# RemoteSch_V2.net
KiCad netlist of a schematic drawn in Altium Designer
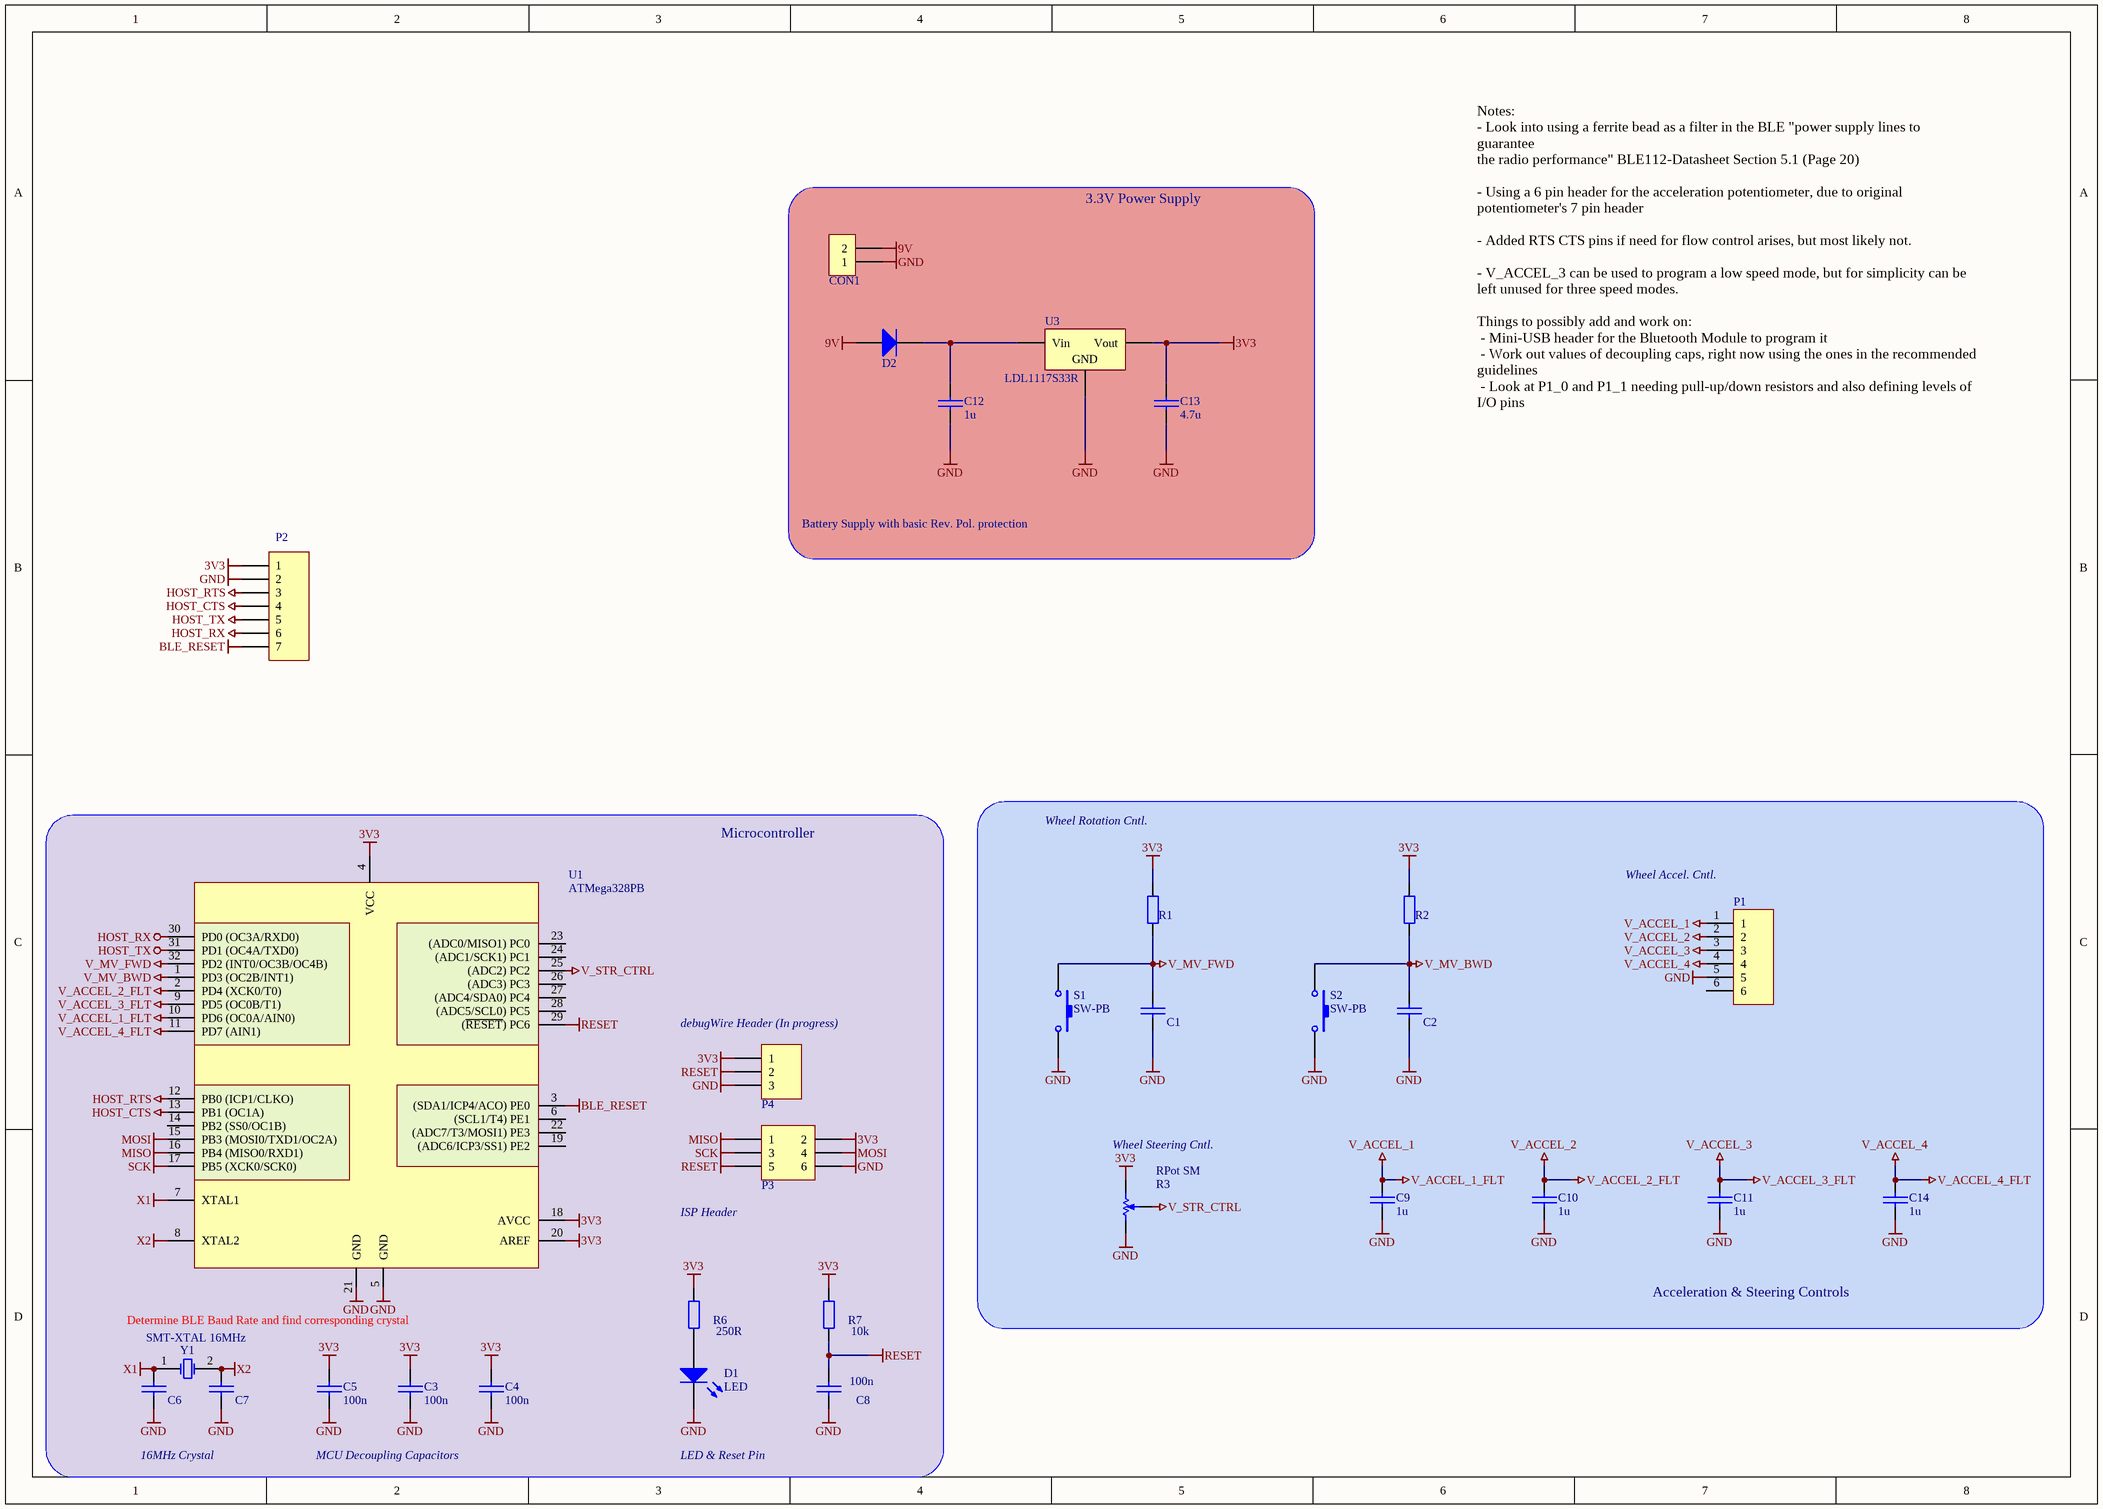
[diagram p0: RemoteSch_V2.SchDoc]

(export (version "E")
  (design (tool "Eeschema 10.0.6"))
  (components
    (comp (ref "C1")
      (value "Capacitor 0805")
      (footprint "C0805")
      (description "CCAP0805")
      (libsource (lib "CommonDevices_V1") (part "CCAP0805"))
    )
    (comp (ref "C2")
      (value "Capacitor 0805")
      (footprint "C0805")
      (description "CCAP0805")
      (libsource (lib "CommonDevices_V1") (part "CCAP0805"))
    )
    (comp (ref "C3")
      (value "100n")
      (footprint "C1206")
      (description "CAP CER 0.1UF 100V C0G 1206")
      (fields (field (name "MPN") "C3216C0G2A104J160AC") (field (name "MANUFACTURER") "TDK Corporation"))
      (libsource (lib "E209_Lib") (part "Cap CER Decoup C3216C0G2A104J160AC"))
    )
    (comp (ref "C4")
      (value "100n")
      (footprint "C1206")
      (description "CAP CER 0.1UF 100V C0G 1206")
      (fields (field (name "MPN") "C3216C0G2A104J160AC") (field (name "MANUFACTURER") "TDK Corporation"))
      (libsource (lib "E209_Lib") (part "Cap CER Decoup C3216C0G2A104J160AC"))
    )
    (comp (ref "C5")
      (value "100n")
      (footprint "C1206")
      (description "CAP CER 0.1UF 100V C0G 1206")
      (fields (field (name "MPN") "C3216C0G2A104J160AC") (field (name "MANUFACTURER") "TDK Corporation"))
      (libsource (lib "E209_Lib") (part "Cap CER Decoup C3216C0G2A104J160AC"))
    )
    (comp (ref "C6")
      (value "CCAP1210")
      (footprint "C1210")
      (fields (field (name "MPN") "?"))
      (libsource (lib "E209_Lib") (part "CCAP1210"))
    )
    (comp (ref "C7")
      (value "CCAP1210")
      (footprint "C1210")
      (fields (field (name "MPN") "?"))
      (libsource (lib "E209_Lib") (part "CCAP1210"))
    )
    (comp (ref "C8")
      (value "100n")
      (footprint "C1210")
      (description "CCAP1210")
      (libsource (lib "CommonDevices_V1") (part "CCAP1210"))
    )
    (comp (ref "C9")
      (value "1u")
      (footprint "C0805")
      (description "CCAP0805")
      (libsource (lib "CommonDevices_V1") (part "CCAP0805"))
    )
    (comp (ref "C10")
      (value "1u")
      (footprint "C0805")
      (description "CCAP0805")
      (libsource (lib "CommonDevices_V1") (part "CCAP0805"))
    )
    (comp (ref "C11")
      (value "1u")
      (footprint "C0805")
      (description "CCAP0805")
      (libsource (lib "CommonDevices_V1") (part "CCAP0805"))
    )
    (comp (ref "C12")
      (value "1u")
      (footprint "C1210")
      (description "CAP CER 2.2UF 100V X7R 1210")
      (fields (field (name "MPN") "CL32B225KCJSNNE") (field (name "MANUFACTURER") "AVX Corporation"))
      (libsource (lib "E209_Lib") (part "Cap CER HF DC-Link CL32B225KCJSNNE"))
    )
    (comp (ref "C13")
      (value "4.7u")
      (footprint "C1210")
      (description "CAP CER 2.2UF 100V X7R 1210")
      (fields (field (name "MPN") "CL32B225KCJSNNE") (field (name "MANUFACTURER") "AVX Corporation"))
      (libsource (lib "E209_Lib") (part "Cap CER HF DC-Link CL32B225KCJSNNE"))
    )
    (comp (ref "C14")
      (value "1u")
      (footprint "C0805")
      (description "CCAP0805")
      (libsource (lib "CommonDevices_V1") (part "CCAP0805"))
    )
    (comp (ref "CON1")
      (value "Header 2X1")
      (footprint "HDR2X1_2P54")
      (libsource (lib "CommonDevices_V1") (part "HDR2X1"))
    )
    (comp (ref "D1") (value "LED") (footprint "R0805") (libsource (lib "CommonDevices_V1") (part "LED")))
    (comp (ref "D2") (value "Diode") (footprint "DAX4") (libsource (lib "CommonDevices_V1") (part "Diode")))
    (comp (ref "P1")
      (value "Header 6X1")
      (footprint "HDR6X1_2P54")
      (description "Header, 6-Pin")
      (fields (field (name "PUBLISHER") "Altium Limited"))
      (libsource (lib "CommonDevices_V1") (part "HDR6X1"))
    )
    (comp (ref "P2")
      (value "Header 7")
      (footprint "HDR1X7")
      (description "Header, 7-Pin")
      (fields (field (name "PUBLISHER") "Altium Limited"))
      (libsource (lib "Miscellaneous Connectors") (part "Header 7"))
    )
    (comp (ref "P3")
      (value "HDR3X2")
      (footprint "HDR2X3_2P54")
      (description "Header, 3-Pin, Dual row")
      (libsource (lib "CommonDevices_V1") (part "HDR3X2"))
    )
    (comp (ref "P4")
      (value "Header 3")
      (footprint "HDR1X3")
      (description "Header, 3-Pin")
      (fields (field (name "PUBLISHER") "Altium Limited"))
      (libsource (lib "Miscellaneous Connectors") (part "Header 3"))
    )
    (comp (ref "R1")
      (value "Resistor 0805")
      (footprint "R0805")
      (description "RES0805")
      (libsource (lib "CommonDevices_V1") (part "RES0805"))
    )
    (comp (ref "R2")
      (value "Resistor 0805")
      (footprint "R0805")
      (description "RES0805")
      (libsource (lib "CommonDevices_V1") (part "RES0805"))
    )
    (comp (ref "R3")
      (value "RPot SM")
      (footprint "POT4MM-2")
      (description "Square Trimming Potentiometer")
      (fields (field (name "PUBLISHER") "Altium Limited"))
      (libsource (lib "Miscellaneous Devices") (part "RPot SM"))
    )
    (comp (ref "R6")
      (value "250R")
      (footprint "R1206")
      (description "RES1206")
      (libsource (lib "CommonDevices_V1") (part "RES1206"))
    )
    (comp (ref "R7")
      (value "10k")
      (footprint "R1206")
      (description "RES1206")
      (libsource (lib "CommonDevices_V1") (part "RES1206"))
    )
    (comp (ref "S1")
      (value "SW-PB")
      (footprint "SPST-2")
      (description "Switch")
      (fields (field (name "PUBLISHER") "Altium Limited"))
      (libsource (lib "Miscellaneous Devices") (part "SW-PB"))
    )
    (comp (ref "S2")
      (value "SW-PB")
      (footprint "SPST-2")
      (description "Switch")
      (fields (field (name "PUBLISHER") "Altium Limited"))
      (libsource (lib "Miscellaneous Devices") (part "SW-PB"))
    )
    (comp (ref "U1")
      (value "ATMega328PB")
      (footprint "TQFP32")
      (description "IC MCU 8BIT 32KB FLASH 32TQFP")
      (libsource (lib "CommonDevices_V1") (part "ATMega328PB"))
    )
    (comp (ref "U3")
      (value "LDL1117S33R")
      (footprint "SOT223L")
      (description "IC REG LINEAR 3.3V 1.2A SOT223")
      (fields (field (name "MANUFACTURER") "STMicroelectronics"))
      (libsource (lib "E209_Lib") (part "LDO LDL1117S33R"))
    )
    (comp (ref "Y1")
      (value "SMT-XTAL 16MHz")
      (footprint "HC49-US")
      (description "9C-16.000MAAJ-T crystal 16.0000MHZ 18PF SMD")
      (fields
        (field (name "MANUFACTURER") "TXC CORPORATION")
        (field (name "MANUFACTURER PART NUMBER") "9C-16.000MAAJ-T")
      )
      (libsource (lib "EE209_Library") (part "TXC9C-16_XTAL_SMT"))
    )
  )
  (nets
    (net (code "1") (name "3V3") (class "Default")
      (node (ref "C13") (pin "2") (pinfunction "2_2") (pintype "passive"))
      (node (ref "C3") (pin "2") (pinfunction "2_2") (pintype "passive"))
      (node (ref "C4") (pin "2") (pinfunction "2_2") (pintype "passive"))
      (node (ref "C5") (pin "2") (pinfunction "2_2") (pintype "passive"))
      (node (ref "P2") (pin "1") (pinfunction "1_1") (pintype "passive"))
      (node (ref "P3") (pin "2") (pinfunction "2_2") (pintype "passive"))
      (node (ref "P4") (pin "1") (pinfunction "1_1") (pintype "passive"))
      (node (ref "R1") (pin "1") (pinfunction "1_1") (pintype "passive"))
      (node (ref "R2") (pin "1") (pinfunction "1_1") (pintype "passive"))
      (node (ref "R3") (pin "CW") (pinfunction "+_CW") (pintype "passive"))
      (node (ref "R6") (pin "2") (pinfunction "2_2") (pintype "passive"))
      (node (ref "R7") (pin "2") (pinfunction "2_2") (pintype "passive"))
      (node (ref "U1") (pin "18") (pinfunction "AVCC_18") (pintype "passive"))
      (node (ref "U1") (pin "20") (pinfunction "AREF_20") (pintype "passive"))
      (node (ref "U1") (pin "4") (pinfunction "VCC_4") (pintype "passive"))
      (node (ref "U3") (pin "2") (pinfunction "Vout_2") (pintype "passive"))
    )
    (net (code "2") (name "9V") (class "Default")
      (node (ref "CON1") (pin "2") (pinfunction "2_2") (pintype "passive"))
      (node (ref "D2") (pin "1") (pinfunction "1_1") (pintype "passive"))
    )
    (net (code "3") (name "BLE_RESET") (class "Default")
      (node (ref "P2") (pin "7") (pinfunction "7_7") (pintype "passive"))
      (node (ref "U1") (pin "3") (pinfunction "(SDA1/ICP4/ACO)_PE0_3") (pintype "passive"))
    )
    (net (code "4") (name "GND") (class "Default")
      (node (ref "C1") (pin "1") (pinfunction "1_1") (pintype "passive"))
      (node (ref "C10") (pin "1") (pinfunction "1_1") (pintype "passive"))
      (node (ref "C11") (pin "1") (pinfunction "1_1") (pintype "passive"))
      (node (ref "C12") (pin "1") (pinfunction "1_1") (pintype "passive"))
      (node (ref "C13") (pin "1") (pinfunction "1_1") (pintype "passive"))
      (node (ref "C14") (pin "1") (pinfunction "1_1") (pintype "passive"))
      (node (ref "C2") (pin "1") (pinfunction "1_1") (pintype "passive"))
      (node (ref "C3") (pin "1") (pinfunction "1_1") (pintype "passive"))
      (node (ref "C4") (pin "1") (pinfunction "1_1") (pintype "passive"))
      (node (ref "C5") (pin "1") (pinfunction "1_1") (pintype "passive"))
      (node (ref "C6") (pin "1") (pinfunction "1_1") (pintype "passive"))
      (node (ref "C7") (pin "1") (pinfunction "1_1") (pintype "passive"))
      (node (ref "C8") (pin "1") (pinfunction "1_1") (pintype "passive"))
      (node (ref "C9") (pin "1") (pinfunction "1_1") (pintype "passive"))
      (node (ref "CON1") (pin "1") (pinfunction "1_1") (pintype "passive"))
      (node (ref "D1") (pin "2") (pinfunction "K_2") (pintype "passive"))
      (node (ref "P1") (pin "5") (pinfunction "5_5") (pintype "passive"))
      (node (ref "P2") (pin "2") (pinfunction "2_2") (pintype "passive"))
      (node (ref "P3") (pin "6") (pinfunction "6_6") (pintype "passive"))
      (node (ref "P4") (pin "3") (pinfunction "3_3") (pintype "passive"))
      (node (ref "R3") (pin "CCW") (pinfunction "-_CCW") (pintype "passive"))
      (node (ref "S1") (pin "2") (pinfunction "2_2") (pintype "passive"))
      (node (ref "S2") (pin "2") (pinfunction "2_2") (pintype "passive"))
      (node (ref "U3") (pin "1") (pinfunction "GND_1") (pintype "passive"))
    )
    (net (code "5") (name "HOST_CTS") (class "Default")
      (node (ref "P2") (pin "4") (pinfunction "4_4") (pintype "passive"))
      (node (ref "U1") (pin "13") (pinfunction "PB1_(OC1A)_13") (pintype "passive"))
    )
    (net (code "6") (name "HOST_RTS") (class "Default")
      (node (ref "P2") (pin "3") (pinfunction "3_3") (pintype "passive"))
      (node (ref "U1") (pin "12") (pinfunction "PB0_(ICP1/CLKO)_12") (pintype "passive"))
    )
    (net (code "7") (name "HOST_RX") (class "Default")
      (node (ref "P2") (pin "6") (pinfunction "6_6") (pintype "passive"))
      (node (ref "U1") (pin "30") (pinfunction "PD0_(OC3A/RXD0)_30") (pintype "passive"))
    )
    (net (code "8") (name "HOST_TX") (class "Default")
      (node (ref "P2") (pin "5") (pinfunction "5_5") (pintype "passive"))
      (node (ref "U1") (pin "31") (pinfunction "PD1_(OC4A/TXD0)_31") (pintype "passive"))
    )
    (net (code "9") (name "MISO") (class "Default")
      (node (ref "P3") (pin "1") (pinfunction "1_1") (pintype "passive"))
      (node (ref "U1") (pin "16") (pinfunction "PB4_(MISO0/RXD1)_16") (pintype "passive"))
    )
    (net (code "10") (name "MOSI") (class "Default")
      (node (ref "P3") (pin "4") (pinfunction "4_4") (pintype "passive"))
      (node (ref "U1") (pin "15") (pinfunction "PB3_(MOSI0/TXD1/OC2A)_15") (pintype "passive"))
    )
    (net (code "11") (name "Net-(D1-A)") (class "Default")
      (node (ref "D1") (pin "1") (pinfunction "A_1") (pintype "passive"))
      (node (ref "R6") (pin "1") (pinfunction "1_1") (pintype "passive"))
    )
    (net (code "12") (name "Net-(U3-Vin)") (class "Default")
      (node (ref "C12") (pin "2") (pinfunction "2_2") (pintype "passive"))
      (node (ref "D2") (pin "2") (pinfunction "2_2") (pintype "passive"))
      (node (ref "U3") (pin "3") (pinfunction "Vin_3") (pintype "passive"))
    )
    (net (code "13") (name "RESET") (class "Default")
      (node (ref "C8") (pin "2") (pinfunction "2_2") (pintype "passive"))
      (node (ref "P3") (pin "5") (pinfunction "5_5") (pintype "passive"))
      (node (ref "P4") (pin "2") (pinfunction "2_2") (pintype "passive"))
      (node (ref "R7") (pin "1") (pinfunction "1_1") (pintype "passive"))
      (node (ref "U1") (pin "29") (pinfunction "(~{RESET})_PC6_29") (pintype "passive"))
    )
    (net (code "14") (name "SCK") (class "Default")
      (node (ref "P3") (pin "3") (pinfunction "3_3") (pintype "passive"))
      (node (ref "U1") (pin "17") (pinfunction "PB5_(XCK0/SCK0)_17") (pintype "passive"))
    )
    (net (code "15") (name "V_ACCEL_1") (class "Default")
      (node (ref "C9") (pin "2") (pinfunction "2_2") (pintype "passive"))
      (node (ref "P1") (pin "1") (pinfunction "1_1") (pintype "passive"))
      (node (ref "U1") (pin "10") (pinfunction "PD6_(OC0A/AIN0)_10") (pintype "passive"))
    )
    (net (code "16") (name "V_ACCEL_2") (class "Default")
      (node (ref "C10") (pin "2") (pinfunction "2_2") (pintype "passive"))
      (node (ref "P1") (pin "2") (pinfunction "2_2") (pintype "passive"))
      (node (ref "U1") (pin "2") (pinfunction "PD4_(XCK0/T0)_2") (pintype "passive"))
    )
    (net (code "17") (name "V_ACCEL_3") (class "Default")
      (node (ref "C11") (pin "2") (pinfunction "2_2") (pintype "passive"))
      (node (ref "P1") (pin "3") (pinfunction "3_3") (pintype "passive"))
      (node (ref "U1") (pin "9") (pinfunction "PD5_(OC0B/T1)_9") (pintype "passive"))
    )
    (net (code "18") (name "V_ACCEL_4") (class "Default")
      (node (ref "C14") (pin "2") (pinfunction "2_2") (pintype "passive"))
      (node (ref "P1") (pin "4") (pinfunction "4_4") (pintype "passive"))
      (node (ref "U1") (pin "11") (pinfunction "PD7_(AIN1)_11") (pintype "passive"))
    )
    (net (code "19") (name "V_MV_BWD") (class "Default")
      (node (ref "C2") (pin "2") (pinfunction "2_2") (pintype "passive"))
      (node (ref "R2") (pin "2") (pinfunction "2_2") (pintype "passive"))
      (node (ref "S2") (pin "1") (pinfunction "1_1") (pintype "passive"))
      (node (ref "U1") (pin "1") (pinfunction "PD3_(OC2B/INT1)_1") (pintype "passive"))
    )
    (net (code "20") (name "V_MV_FWD") (class "Default")
      (node (ref "C1") (pin "2") (pinfunction "2_2") (pintype "passive"))
      (node (ref "R1") (pin "2") (pinfunction "2_2") (pintype "passive"))
      (node (ref "S1") (pin "1") (pinfunction "1_1") (pintype "passive"))
      (node (ref "U1") (pin "32") (pinfunction "PD2_(INT0/OC3B/OC4B)_32") (pintype "passive"))
    )
    (net (code "21") (name "V_STR_CTRL") (class "Default")
      (node (ref "R3") (pin "W") (pinfunction "W_W") (pintype "passive"))
      (node (ref "U1") (pin "25") (pinfunction "(ADC2)_PC2_25") (pintype "passive"))
    )
    (net (code "22") (name "X1") (class "Default")
      (node (ref "C6") (pin "2") (pinfunction "2_2") (pintype "passive"))
      (node (ref "U1") (pin "7") (pinfunction "XTAL1_7") (pintype "passive"))
      (node (ref "Y1") (pin "1") (pinfunction "OSC1_1") (pintype "passive"))
    )
    (net (code "23") (name "X2") (class "Default")
      (node (ref "C7") (pin "2") (pinfunction "2_2") (pintype "passive"))
      (node (ref "U1") (pin "8") (pinfunction "XTAL2_8") (pintype "passive"))
      (node (ref "Y1") (pin "2") (pinfunction "OSC2_2") (pintype "passive"))
    )
    (net (code "24") (name "unconnected-(P1-Pad6)") (class "Default")
      (node (ref "P1") (pin "6") (pinfunction "6_6") (pintype "passive"))
    )
    (net (code "25") (name "unconnected-(U1-(ADC0{slash}MISO1)_PC0-Pad23)") (class "Default")
      (node (ref "U1") (pin "23") (pinfunction "(ADC0/MISO1)_PC0_23") (pintype "passive"))
    )
    (net (code "26") (name "unconnected-(U1-(ADC1{slash}SCK1)_PC1-Pad24)") (class "Default")
      (node (ref "U1") (pin "24") (pinfunction "(ADC1/SCK1)_PC1_24") (pintype "passive"))
    )
    (net (code "27") (name "unconnected-(U1-(ADC3)_PC3-Pad26)") (class "Default")
      (node (ref "U1") (pin "26") (pinfunction "(ADC3)_PC3_26") (pintype "passive"))
    )
    (net (code "28") (name "unconnected-(U1-(ADC4{slash}SDA0)_PC4-Pad27)") (class "Default")
      (node (ref "U1") (pin "27") (pinfunction "(ADC4/SDA0)_PC4_27") (pintype "passive"))
    )
    (net (code "29") (name "unconnected-(U1-(ADC5{slash}SCL0)_PC5-Pad28)") (class "Default")
      (node (ref "U1") (pin "28") (pinfunction "(ADC5/SCL0)_PC5_28") (pintype "passive"))
    )
    (net (code "30") (name "unconnected-(U1-(ADC6{slash}ICP3{slash}SS1)_PE2-Pad19)") (class "Default")
      (node (ref "U1") (pin "19") (pinfunction "(ADC6/ICP3/SS1)_PE2_19") (pintype "passive"))
    )
    (net (code "31") (name "unconnected-(U1-(ADC7{slash}T3{slash}MOSI1)_PE3-Pad22)") (class "Default")
      (node (ref "U1") (pin "22") (pinfunction "(ADC7/T3/MOSI1)_PE3_22") (pintype "passive"))
    )
    (net (code "32") (name "unconnected-(U1-(SCL1{slash}T4)_PE1-Pad6)") (class "Default")
      (node (ref "U1") (pin "6") (pinfunction "(SCL1/T4)_PE1_6") (pintype "passive"))
    )
    (net (code "33") (name "unconnected-(U1-GND-Pad5)") (class "Default")
      (node (ref "U1") (pin "5") (pinfunction "GND_5") (pintype "passive"))
    )
    (net (code "34") (name "unconnected-(U1-GND-Pad21)") (class "Default")
      (node (ref "U1") (pin "21") (pinfunction "GND_21") (pintype "passive"))
    )
    (net (code "35") (name "unconnected-(U1-PB2_(SS0{slash}OC1B)-Pad14)") (class "Default")
      (node (ref "U1") (pin "14") (pinfunction "PB2_(SS0/OC1B)_14") (pintype "passive"))
    )
  )
)
